# PWR_SEPIC_N6V.net
KiCad netlist of a schematic drawn in Altium Designer
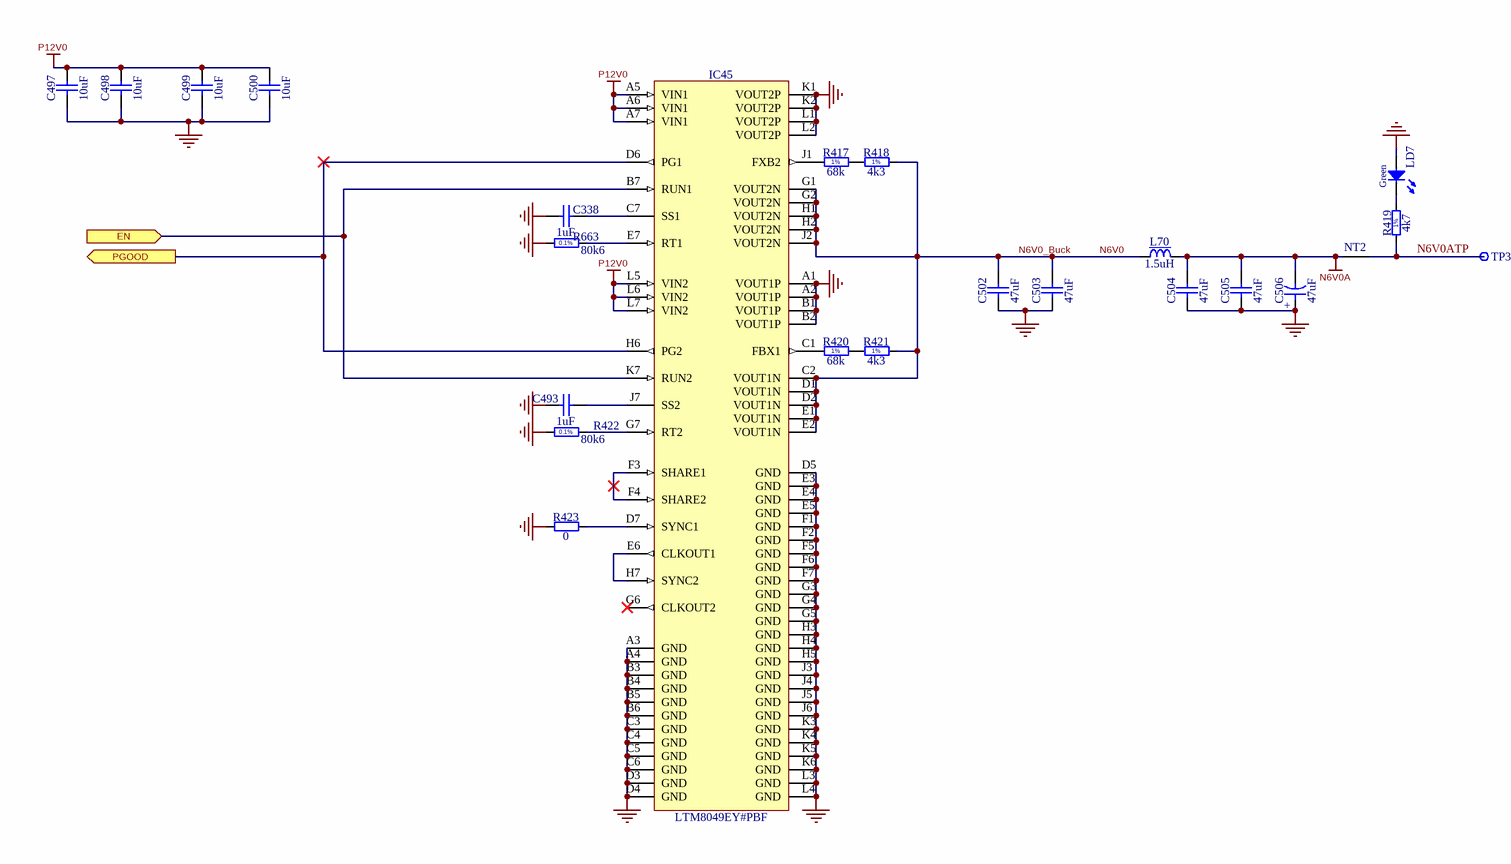
[diagram p0: PWR_SEPIC_N6V.SchDoc]

(export (version "E")
  (design (tool "Eeschema 10.0.6"))
  (components
    (comp (ref "C338")
      (value "1uF")
      (footprint "CAPC1005X55N")
      (description "Non-polarised capacitor")
      (fields
        (field (name "MANUFACTURER PART NUMBER") "CC0402_1UF_16V_10%_X5R")
        (field (name "MANUFACTURER") "GENERIC")
        (field (name "AUTHOR") "CERN DEM JLC")
      )
      (libsource (lib "Capacitors") (part "Capacitor - non polarized"))
    )
    (comp (ref "C493")
      (value "1uF")
      (footprint "CAPC1005X55N")
      (description "Non-polarised capacitor")
      (fields
        (field (name "MANUFACTURER PART NUMBER") "CC0402_1UF_16V_10%_X5R")
        (field (name "MANUFACTURER") "GENERIC")
        (field (name "AUTHOR") "CERN DEM JLC")
      )
      (libsource (lib "Capacitors") (part "Capacitor - non polarized"))
    )
    (comp (ref "C497")
      (value "10uF")
      (footprint "CAPC2012X95N")
      (description "Non-polarised capacitor")
      (fields
        (field (name "MANUFACTURER PART NUMBER") "CC0805_10UF_25V_10%_X5R")
        (field (name "MANUFACTURER") "GENERIC")
        (field (name "AUTHOR") "CERN DEM JLC")
      )
      (libsource (lib "Capacitors") (part "Capacitor - non polarized"))
    )
    (comp (ref "C498")
      (value "10uF")
      (footprint "CAPC2012X95N")
      (description "Non-polarised capacitor")
      (fields
        (field (name "MANUFACTURER PART NUMBER") "CC0805_10UF_25V_10%_X5R")
        (field (name "MANUFACTURER") "GENERIC")
        (field (name "AUTHOR") "CERN DEM JLC")
      )
      (libsource (lib "Capacitors") (part "Capacitor - non polarized"))
    )
    (comp (ref "C499")
      (value "10uF")
      (footprint "CAPC2012X95N")
      (description "Non-polarised capacitor")
      (fields
        (field (name "MANUFACTURER PART NUMBER") "CC0805_10UF_25V_10%_X5R")
        (field (name "MANUFACTURER") "GENERIC")
        (field (name "AUTHOR") "CERN DEM JLC")
      )
      (libsource (lib "Capacitors") (part "Capacitor - non polarized"))
    )
    (comp (ref "C500")
      (value "10uF")
      (footprint "CAPC2012X95N")
      (description "Non-polarised capacitor")
      (fields
        (field (name "MANUFACTURER PART NUMBER") "CC0805_10UF_25V_10%_X5R")
        (field (name "MANUFACTURER") "GENERIC")
        (field (name "AUTHOR") "CERN DEM JLC")
      )
      (libsource (lib "Capacitors") (part "Capacitor - non polarized"))
    )
    (comp (ref "C502")
      (value "47uF")
      (footprint "CAPC3225X270N")
      (description "Non-polarised capacitor")
      (fields
        (field (name "MANUFACTURER PART NUMBER") "CC1210_47UF_10V_10%_X7R")
        (field (name "MANUFACTURER") "GENERIC")
        (field (name "AUTHOR") "CERN DEM BC")
      )
      (libsource (lib "Capacitors") (part "Capacitor - non polarized"))
    )
    (comp (ref "C503")
      (value "47uF")
      (footprint "CAPC3225X270N")
      (description "Non-polarised capacitor")
      (fields
        (field (name "MANUFACTURER PART NUMBER") "CC1210_47UF_10V_10%_X7R")
        (field (name "MANUFACTURER") "GENERIC")
        (field (name "AUTHOR") "CERN DEM BC")
      )
      (libsource (lib "Capacitors") (part "Capacitor - non polarized"))
    )
    (comp (ref "C504")
      (value "47uF")
      (footprint "CAPC3225X270N")
      (description "Non-polarised capacitor")
      (fields
        (field (name "MANUFACTURER PART NUMBER") "CC1210_47UF_10V_10%_X7R")
        (field (name "MANUFACTURER") "GENERIC")
        (field (name "AUTHOR") "CERN DEM BC")
      )
      (libsource (lib "Capacitors") (part "Capacitor - non polarized"))
    )
    (comp (ref "C505")
      (value "47uF")
      (footprint "CAPC3225X270N")
      (description "Non-polarised capacitor")
      (fields
        (field (name "MANUFACTURER PART NUMBER") "CC1210_47UF_10V_10%_X7R")
        (field (name "MANUFACTURER") "GENERIC")
        (field (name "AUTHOR") "CERN DEM BC")
      )
      (libsource (lib "Capacitors") (part "Capacitor - non polarized"))
    )
    (comp (ref "C506")
      (value "47uF")
      (footprint "CAPMP6032X280N")
      (description "Polarised capacitor")
      (fields
        (field (name "MANUFACTURER PART NUMBER") "CTE6032-28_47UF_16V_10%_LESR0350")
        (field (name "MANUFACTURER") "GENERIC")
        (field (name "AUTHOR") "CERN DEM JLC")
      )
      (libsource (lib "Capacitors") (part "Capacitor - polarized"))
    )
    (comp (ref "IC45")
      (value "LTM8049EY#PBF")
      (footprint "BGA77C127P7X11_900X1500X262")
      (description "Dual SEPIC or Inverting uModule DC/DC Converter")
      (fields (field (name "MANUFACTURER") "LINEAR TECHNOLOGY") (field (name "AUTHOR") "CERN DEM JLC"))
      (libsource (lib "ICs And Semiconductors") (part "LTM8049"))
    )
    (comp (ref "L70")
      (value "1.5uH")
      (footprint "IND_TDK_SPM6530")
      (description "Inductor With Core")
      (fields
        (field (name "MANUFACTURER PART NUMBER") "SPM6530T-1R5M100")
        (field (name "MANUFACTURER") "TDK")
        (field (name "AUTHOR") "CERN DEM MR")
      )
      (libsource (lib "Inductors & Transformers") (part "Inductor With Magnetic core"))
    )
    (comp (ref "LD7")
      (value "Green")
      (footprint "LED_KINGBRIGHT_KPH-1608CGCK")
      (description "LED Green 1C 2A")
      (fields
        (field (name "PART NUMBER") "LED_KINGBRIGHT_KPH-1608CGCK")
        (field (name "MANUFACTURER") "KINGBRIGHT")
        (field (name "AUTHOR") "CERN DEM JLC")
      )
      (libsource (lib "ICs And Semiconductors") (part "LED Green 1C 2A"))
    )
    (comp (ref "NT2")
      (value "Net Tie")
      (footprint "Net Tie")
      (fields (field (name "AUTHOR") "CERN DEM JLC"))
      (libsource (lib "Eletro-mechanical") (part "Net Tie"))
    )
    (comp (ref "R417")
      (value "68k")
      (footprint "RESC1005X40N")
      (description "Resistor - 1%")
      (fields
        (field (name "MANUFACTURER PART NUMBER") "R0402_68K_1%_0.0625W_100PPM")
        (field (name "MANUFACTURER") "GENERIC")
        (field (name "AUTHOR") "CERN DEM JLC")
      )
      (libsource (lib "Resistors") (part "Resistor - 1%"))
    )
    (comp (ref "R418")
      (value "4k3")
      (footprint "RESC1005X40N")
      (description "Resistor - 1%")
      (fields
        (field (name "MANUFACTURER PART NUMBER") "R0402_4K3_1%_0.0625W_100PPM")
        (field (name "MANUFACTURER") "GENERIC")
        (field (name "AUTHOR") "CERN DEM JLC")
      )
      (libsource (lib "Resistors") (part "Resistor - 1%"))
    )
    (comp (ref "R419")
      (value "4k7")
      (footprint "RESC1005X40N")
      (description "Resistor - 1%")
      (fields
        (field (name "MANUFACTURER PART NUMBER") "R0402_4K7_1%_0.0625W_100PPM")
        (field (name "MANUFACTURER") "GENERIC")
        (field (name "AUTHOR") "CERN DEM JLC")
      )
      (libsource (lib "Resistors") (part "Resistor - 1%"))
    )
    (comp (ref "R420")
      (value "68k")
      (footprint "RESC1005X40N")
      (description "Resistor - 1%")
      (fields
        (field (name "MANUFACTURER PART NUMBER") "R0402_68K_1%_0.0625W_100PPM")
        (field (name "MANUFACTURER") "GENERIC")
        (field (name "AUTHOR") "CERN DEM JLC")
      )
      (libsource (lib "Resistors") (part "Resistor - 1%"))
    )
    (comp (ref "R421")
      (value "4k3")
      (footprint "RESC1005X40N")
      (description "Resistor - 1%")
      (fields
        (field (name "MANUFACTURER PART NUMBER") "R0402_4K3_1%_0.0625W_100PPM")
        (field (name "MANUFACTURER") "GENERIC")
        (field (name "AUTHOR") "CERN DEM JLC")
      )
      (libsource (lib "Resistors") (part "Resistor - 1%"))
    )
    (comp (ref "R422")
      (value "80k6")
      (footprint "RESC1608X55N")
      (description "Resistor - 0.1%")
      (fields
        (field (name "MANUFACTURER PART NUMBER") "R0603_80K6_0.1%_0.063W_10PPM")
        (field (name "MANUFACTURER") "GENERIC")
        (field (name "AUTHOR") "CERN DEM JLC")
      )
      (libsource (lib "Resistors") (part "Resistor - 0.1%"))
    )
    (comp (ref "R423")
      (value "0")
      (footprint "RESC1005X40N")
      (description "Resistor")
      (fields
        (field (name "MANUFACTURER PART NUMBER") "R0402_0R_JUMPER")
        (field (name "MANUFACTURER") "GENERIC")
        (field (name "AUTHOR") "CERN DEM JLC")
      )
      (libsource (lib "Resistors") (part "Resistor"))
    )
    (comp (ref "R663")
      (value "80k6")
      (footprint "RESC1608X55N")
      (description "Resistor - 0.1%")
      (fields
        (field (name "MANUFACTURER PART NUMBER") "R0603_80K6_0.1%_0.063W_10PPM")
        (field (name "MANUFACTURER") "GENERIC")
        (field (name "AUTHOR") "CERN DEM JLC")
      )
      (libsource (lib "Resistors") (part "Resistor - 0.1%"))
    )
    (comp (ref "TP36")
      (value "Test Point")
      (footprint "TPS127")
      (fields (field (name "PART NUMBER") "SMD_PAD_1.27X1.27MM") (field (name "AUTHOR") "CERN DEM JLC"))
      (libsource (lib "Eletro-mechanical") (part "Test Point"))
    )
  )
  (nets
    (net (code "1") (name "/EN") (class "Default")
      (node (ref "IC45") (pin "B7") (pinfunction "RUN1_B7") (pintype "input"))
      (node (ref "IC45") (pin "K7") (pinfunction "RUN2_K7") (pintype "input"))
    )
    (net (code "2") (name "/N6V0") (class "Default")
      (node (ref "C502") (pin "2") (pinfunction "2_2") (pintype "passive"))
      (node (ref "C503") (pin "2") (pinfunction "2_2") (pintype "passive"))
      (node (ref "IC45") (pin "C2") (pinfunction "VOUT1N_C2") (pintype "power_in"))
      (node (ref "IC45") (pin "D1") (pinfunction "VOUT1N_D1") (pintype "power_in"))
      (node (ref "IC45") (pin "D2") (pinfunction "VOUT1N_D2") (pintype "power_in"))
      (node (ref "IC45") (pin "E1") (pinfunction "VOUT1N_E1") (pintype "power_in"))
      (node (ref "IC45") (pin "E2") (pinfunction "VOUT1N_E2") (pintype "power_in"))
      (node (ref "IC45") (pin "G1") (pinfunction "VOUT2N_G1") (pintype "power_in"))
      (node (ref "IC45") (pin "G2") (pinfunction "VOUT2N_G2") (pintype "power_in"))
      (node (ref "IC45") (pin "H1") (pinfunction "VOUT2N_H1") (pintype "power_in"))
      (node (ref "IC45") (pin "H2") (pinfunction "VOUT2N_H2") (pintype "power_in"))
      (node (ref "IC45") (pin "J2") (pinfunction "VOUT2N_J2") (pintype "power_in"))
      (node (ref "L70") (pin "1") (pinfunction "1_1") (pintype "passive"))
      (node (ref "R418") (pin "2") (pinfunction "2_2") (pintype "passive"))
      (node (ref "R421") (pin "2") (pinfunction "2_2") (pintype "passive"))
    )
    (net (code "3") (name "/N6V0ATP") (class "Default")
      (node (ref "NT2") (pin "2") (pinfunction "2_2") (pintype "bidirectional"))
      (node (ref "R419") (pin "1") (pinfunction "1_1") (pintype "passive"))
      (node (ref "TP36") (pin "1") (pinfunction "1_1") (pintype "bidirectional"))
    )
    (net (code "4") (name "/PGOOD") (class "Default")
      (node (ref "IC45") (pin "D6") (pinfunction "PG1_D6") (pintype "output"))
      (node (ref "IC45") (pin "H6") (pinfunction "PG2_H6") (pintype "output"))
    )
    (net (code "5") (name "GND") (class "Default")
      (node (ref "C338") (pin "2") (pinfunction "2_2") (pintype "passive"))
      (node (ref "C493") (pin "2") (pinfunction "2_2") (pintype "passive"))
      (node (ref "C497") (pin "1") (pinfunction "1_1") (pintype "passive"))
      (node (ref "C498") (pin "1") (pinfunction "1_1") (pintype "passive"))
      (node (ref "C499") (pin "1") (pinfunction "1_1") (pintype "passive"))
      (node (ref "C500") (pin "1") (pinfunction "1_1") (pintype "passive"))
      (node (ref "C502") (pin "1") (pinfunction "1_1") (pintype "passive"))
      (node (ref "C503") (pin "1") (pinfunction "1_1") (pintype "passive"))
      (node (ref "C504") (pin "1") (pinfunction "1_1") (pintype "passive"))
      (node (ref "C505") (pin "1") (pinfunction "1_1") (pintype "passive"))
      (node (ref "C506") (pin "1") (pinfunction "1_1") (pintype "passive"))
      (node (ref "IC45") (pin "A1") (pinfunction "VOUT1P_A1") (pintype "power_in"))
      (node (ref "IC45") (pin "A2") (pinfunction "VOUT1P_A2") (pintype "power_in"))
      (node (ref "IC45") (pin "A3") (pinfunction "GND_A3") (pintype "power_in"))
      (node (ref "IC45") (pin "A4") (pinfunction "GND_A4") (pintype "power_in"))
      (node (ref "IC45") (pin "B1") (pinfunction "VOUT1P_B1") (pintype "power_in"))
      (node (ref "IC45") (pin "B2") (pinfunction "VOUT1P_B2") (pintype "power_in"))
      (node (ref "IC45") (pin "B3") (pinfunction "GND_B3") (pintype "power_in"))
      (node (ref "IC45") (pin "B4") (pinfunction "GND_B4") (pintype "power_in"))
      (node (ref "IC45") (pin "B5") (pinfunction "GND_B5") (pintype "power_in"))
      (node (ref "IC45") (pin "B6") (pinfunction "GND_B6") (pintype "power_in"))
      (node (ref "IC45") (pin "C3") (pinfunction "GND_C3") (pintype "power_in"))
      (node (ref "IC45") (pin "C4") (pinfunction "GND_C4") (pintype "power_in"))
      (node (ref "IC45") (pin "C5") (pinfunction "GND_C5") (pintype "power_in"))
      (node (ref "IC45") (pin "C6") (pinfunction "GND_C6") (pintype "power_in"))
      (node (ref "IC45") (pin "D3") (pinfunction "GND_D3") (pintype "power_in"))
      (node (ref "IC45") (pin "D4") (pinfunction "GND_D4") (pintype "power_in"))
      (node (ref "IC45") (pin "D5") (pinfunction "GND_D5") (pintype "power_in"))
      (node (ref "IC45") (pin "E3") (pinfunction "GND_E3") (pintype "power_in"))
      (node (ref "IC45") (pin "E4") (pinfunction "GND_E4") (pintype "power_in"))
      (node (ref "IC45") (pin "E5") (pinfunction "GND_E5") (pintype "power_in"))
      (node (ref "IC45") (pin "F1") (pinfunction "GND_F1") (pintype "power_in"))
      (node (ref "IC45") (pin "F2") (pinfunction "GND_F2") (pintype "power_in"))
      (node (ref "IC45") (pin "F5") (pinfunction "GND_F5") (pintype "power_in"))
      (node (ref "IC45") (pin "F6") (pinfunction "GND_F6") (pintype "power_in"))
      (node (ref "IC45") (pin "F7") (pinfunction "GND_F7") (pintype "power_in"))
      (node (ref "IC45") (pin "G3") (pinfunction "GND_G3") (pintype "power_in"))
      (node (ref "IC45") (pin "G4") (pinfunction "GND_G4") (pintype "power_in"))
      (node (ref "IC45") (pin "G5") (pinfunction "GND_G5") (pintype "power_in"))
      (node (ref "IC45") (pin "H3") (pinfunction "GND_H3") (pintype "power_in"))
      (node (ref "IC45") (pin "H4") (pinfunction "GND_H4") (pintype "power_in"))
      (node (ref "IC45") (pin "H5") (pinfunction "GND_H5") (pintype "power_in"))
      (node (ref "IC45") (pin "J3") (pinfunction "GND_J3") (pintype "power_in"))
      (node (ref "IC45") (pin "J4") (pinfunction "GND_J4") (pintype "power_in"))
      (node (ref "IC45") (pin "J5") (pinfunction "GND_J5") (pintype "power_in"))
      (node (ref "IC45") (pin "J6") (pinfunction "GND_J6") (pintype "power_in"))
      (node (ref "IC45") (pin "K1") (pinfunction "VOUT2P_K1") (pintype "power_in"))
      (node (ref "IC45") (pin "K2") (pinfunction "VOUT2P_K2") (pintype "power_in"))
      (node (ref "IC45") (pin "K3") (pinfunction "GND_K3") (pintype "power_in"))
      (node (ref "IC45") (pin "K4") (pinfunction "GND_K4") (pintype "power_in"))
      (node (ref "IC45") (pin "K5") (pinfunction "GND_K5") (pintype "power_in"))
      (node (ref "IC45") (pin "K6") (pinfunction "GND_K6") (pintype "power_in"))
      (node (ref "IC45") (pin "L1") (pinfunction "VOUT2P_L1") (pintype "power_in"))
      (node (ref "IC45") (pin "L2") (pinfunction "VOUT2P_L2") (pintype "power_in"))
      (node (ref "IC45") (pin "L3") (pinfunction "GND_L3") (pintype "power_in"))
      (node (ref "IC45") (pin "L4") (pinfunction "GND_L4") (pintype "power_in"))
      (node (ref "LD7") (pin "2") (pinfunction "A_2") (pintype "passive"))
      (node (ref "R422") (pin "1") (pinfunction "1_1") (pintype "passive"))
      (node (ref "R423") (pin "1") (pinfunction "1_1") (pintype "passive"))
      (node (ref "R663") (pin "1") (pinfunction "1_1") (pintype "passive"))
    )
    (net (code "6") (name "N6V0A") (class "Default")
      (node (ref "C504") (pin "2") (pinfunction "2_2") (pintype "passive"))
      (node (ref "C505") (pin "2") (pinfunction "2_2") (pintype "passive"))
      (node (ref "C506") (pin "2") (pinfunction "2_2") (pintype "passive"))
      (node (ref "L70") (pin "2") (pinfunction "2_2") (pintype "passive"))
      (node (ref "NT2") (pin "1") (pinfunction "1_1") (pintype "bidirectional"))
    )
    (net (code "7") (name "Net-(IC45-CLKOUT1)") (class "Default")
      (node (ref "IC45") (pin "E6") (pinfunction "CLKOUT1_E6") (pintype "output"))
      (node (ref "IC45") (pin "H7") (pinfunction "SYNC2_H7") (pintype "input"))
    )
    (net (code "8") (name "Net-(IC45-FBX1)") (class "Default")
      (node (ref "IC45") (pin "C1") (pinfunction "FBX1_C1") (pintype "output"))
      (node (ref "R420") (pin "1") (pinfunction "1_1") (pintype "passive"))
    )
    (net (code "9") (name "Net-(IC45-FXB2)") (class "Default")
      (node (ref "IC45") (pin "J1") (pinfunction "FXB2_J1") (pintype "output"))
      (node (ref "R417") (pin "1") (pinfunction "1_1") (pintype "passive"))
    )
    (net (code "10") (name "Net-(IC45-RT1)") (class "Default")
      (node (ref "IC45") (pin "E7") (pinfunction "RT1_E7") (pintype "input"))
      (node (ref "R663") (pin "2") (pinfunction "2_2") (pintype "passive"))
    )
    (net (code "11") (name "Net-(IC45-RT2)") (class "Default")
      (node (ref "IC45") (pin "G7") (pinfunction "RT2_G7") (pintype "input"))
      (node (ref "R422") (pin "2") (pinfunction "2_2") (pintype "passive"))
    )
    (net (code "12") (name "Net-(IC45-SHARE1)") (class "Default")
      (node (ref "IC45") (pin "F3") (pinfunction "SHARE1_F3") (pintype "input"))
      (node (ref "IC45") (pin "F4") (pinfunction "SHARE2_F4") (pintype "input"))
    )
    (net (code "13") (name "Net-(IC45-SS1)") (class "Default")
      (node (ref "C338") (pin "1") (pinfunction "1_1") (pintype "passive"))
      (node (ref "IC45") (pin "C7") (pinfunction "SS1_C7") (pintype "passive"))
    )
    (net (code "14") (name "Net-(IC45-SS2)") (class "Default")
      (node (ref "C493") (pin "1") (pinfunction "1_1") (pintype "passive"))
      (node (ref "IC45") (pin "J7") (pinfunction "SS2_J7") (pintype "passive"))
    )
    (net (code "15") (name "Net-(IC45-SYNC1)") (class "Default")
      (node (ref "IC45") (pin "D7") (pinfunction "SYNC1_D7") (pintype "input"))
      (node (ref "R423") (pin "2") (pinfunction "2_2") (pintype "passive"))
    )
    (net (code "16") (name "Net-(LD7-C)") (class "Default")
      (node (ref "LD7") (pin "1") (pinfunction "C_1") (pintype "passive"))
      (node (ref "R419") (pin "2") (pinfunction "2_2") (pintype "passive"))
    )
    (net (code "17") (name "Net-(R417-Pad2)") (class "Default")
      (node (ref "R417") (pin "2") (pinfunction "2_2") (pintype "passive"))
      (node (ref "R418") (pin "1") (pinfunction "1_1") (pintype "passive"))
    )
    (net (code "18") (name "Net-(R420-Pad2)") (class "Default")
      (node (ref "R420") (pin "2") (pinfunction "2_2") (pintype "passive"))
      (node (ref "R421") (pin "1") (pinfunction "1_1") (pintype "passive"))
    )
    (net (code "19") (name "P12V0") (class "Default")
      (node (ref "C497") (pin "2") (pinfunction "2_2") (pintype "passive"))
      (node (ref "C498") (pin "2") (pinfunction "2_2") (pintype "passive"))
      (node (ref "C499") (pin "2") (pinfunction "2_2") (pintype "passive"))
      (node (ref "C500") (pin "2") (pinfunction "2_2") (pintype "passive"))
      (node (ref "IC45") (pin "A5") (pinfunction "VIN1_A5") (pintype "input"))
      (node (ref "IC45") (pin "A6") (pinfunction "VIN1_A6") (pintype "input"))
      (node (ref "IC45") (pin "A7") (pinfunction "VIN1_A7") (pintype "input"))
      (node (ref "IC45") (pin "L5") (pinfunction "VIN2_L5") (pintype "input"))
      (node (ref "IC45") (pin "L6") (pinfunction "VIN2_L6") (pintype "input"))
      (node (ref "IC45") (pin "L7") (pinfunction "VIN2_L7") (pintype "input"))
    )
    (net (code "20") (name "unconnected-(IC45-CLKOUT2-PadG6)") (class "Default")
      (node (ref "IC45") (pin "G6") (pinfunction "CLKOUT2_G6") (pintype "output+no_connect"))
    )
  )
)
